# v1.net
KiCad netlist of a schematic drawn in EAGLE
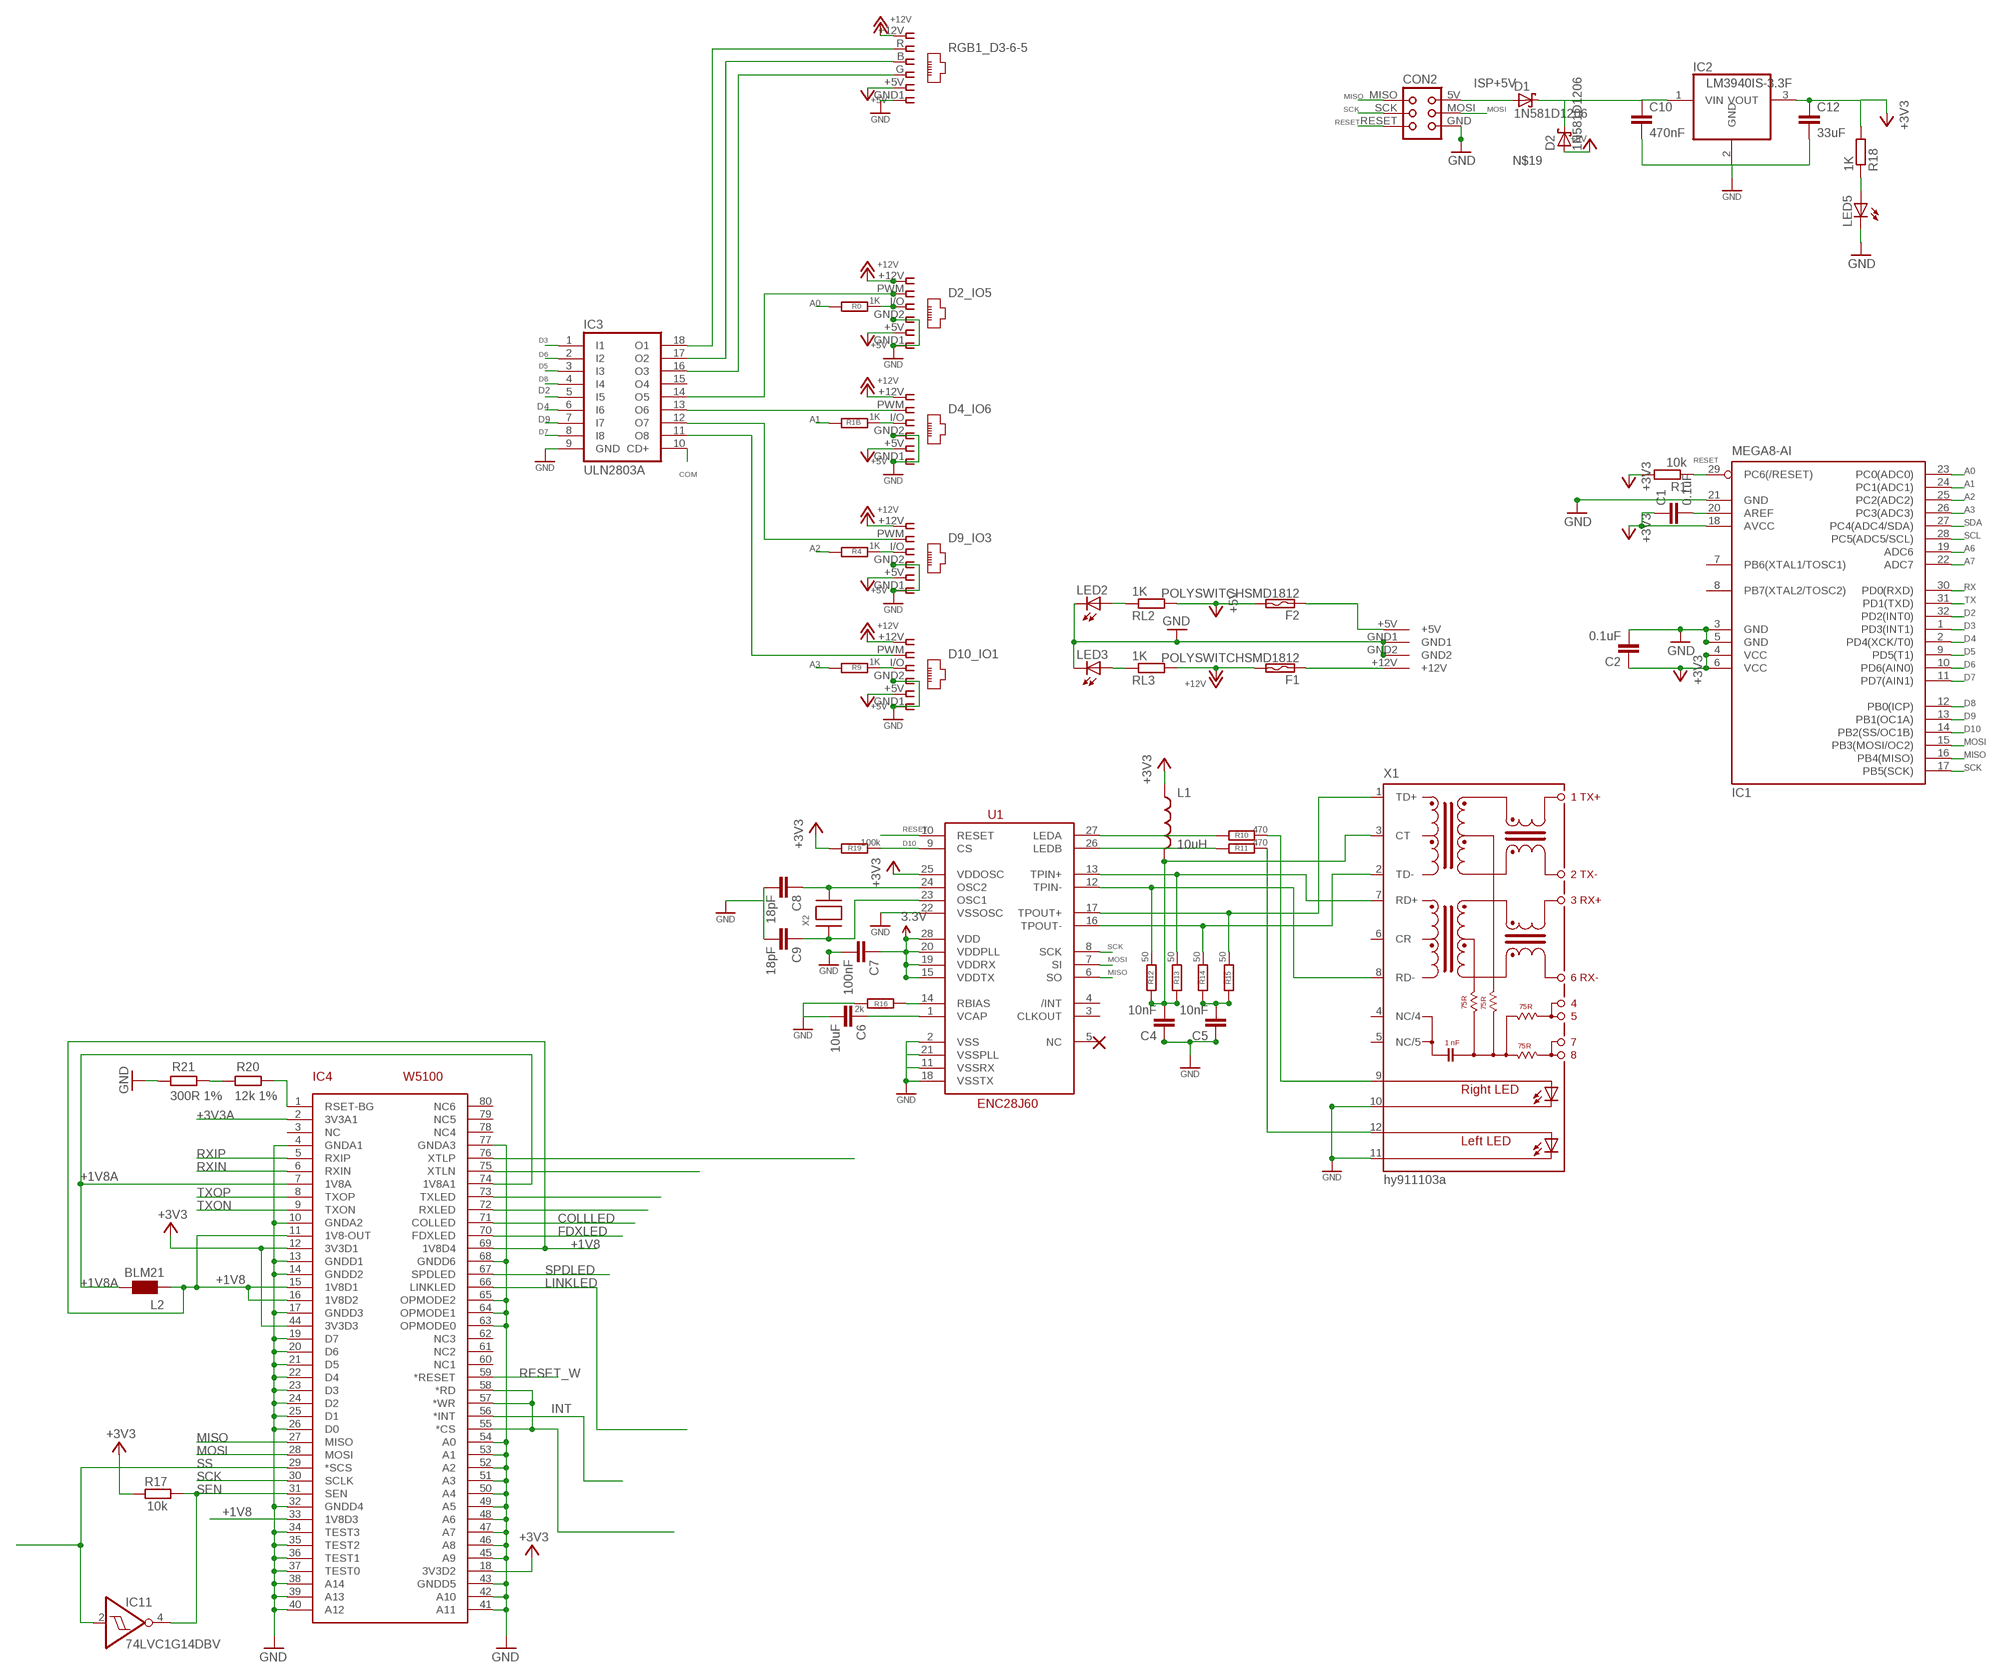
[diagram p0: schematic, sheet 1, part 1 of 2]
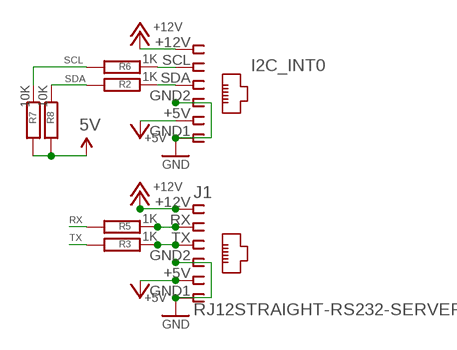
[diagram p1: schematic, sheet 1, part 2 of 2]

(export (version "E")
  (design (tool "Eeschema 10.0.6"))
  (components
    (comp (ref "C1")
      (value "0.1uF")
      (footprint "eagle-import:C1206")
      (libsource (lib "eagle-import") (part "resistor_C-EUC1206"))
    )
    (comp (ref "C2")
      (value "0.1uF")
      (footprint "eagle-import:C1206")
      (libsource (lib "eagle-import") (part "resistor_C-EUC1206"))
    )
    (comp (ref "C4")
      (value "10nF")
      (footprint "eagle-import:C1206")
      (libsource (lib "eagle-import") (part "resistor_C-EUC1206"))
    )
    (comp (ref "C5")
      (value "10nF")
      (footprint "eagle-import:C1206")
      (libsource (lib "eagle-import") (part "resistor_C-EUC1206"))
    )
    (comp (ref "C6")
      (value "10uF")
      (footprint "eagle-import:C1206")
      (libsource (lib "eagle-import") (part "resistor_C-EUC1206"))
    )
    (comp (ref "C7")
      (value "100nF")
      (footprint "eagle-import:C1206")
      (libsource (lib "eagle-import") (part "resistor_C-EUC1206"))
    )
    (comp (ref "C8")
      (value "18pF")
      (footprint "eagle-import:C1206")
      (libsource (lib "eagle-import") (part "resistor_C-EUC1206"))
    )
    (comp (ref "C9")
      (value "18pF")
      (footprint "eagle-import:C1206")
      (libsource (lib "eagle-import") (part "resistor_C-EUC1206"))
    )
    (comp (ref "C10")
      (value "470nF")
      (footprint "eagle-import:C1206")
      (libsource (lib "eagle-import") (part "C-EUC1206"))
    )
    (comp (ref "C12")
      (value "33uF")
      (footprint "eagle-import:1210")
      (libsource (lib "eagle-import") (part "CAP1210"))
    )
    (comp (ref "CON2")
      (value "TINYISPTAG")
      (footprint "eagle-import:TC2030-MCP")
      (libsource (lib "eagle-import") (part "TINYISPTAG"))
    )
    (comp (ref "D1")
      (value "1N581D1206")
      (footprint "eagle-import:LED-1206")
      (libsource (lib "eagle-import") (part "1N581D1206"))
    )
    (comp (ref "D2")
      (value "1N581D1206")
      (footprint "eagle-import:LED-1206")
      (libsource (lib "eagle-import") (part "1N581D1206"))
    )
    (comp (ref "D2_IO5")
      (value "IO5")
      (footprint "eagle-import:RJ12-STRAIGHT")
      (libsource (lib "eagle-import") (part "RJ12STRAIGHT"))
    )
    (comp (ref "D4_IO6")
      (value "IO6")
      (footprint "eagle-import:RJ12-STRAIGHT")
      (libsource (lib "eagle-import") (part "RJ12STRAIGHT"))
    )
    (comp (ref "D9_IO3")
      (value "IO3")
      (footprint "eagle-import:RJ12-STRAIGHT")
      (libsource (lib "eagle-import") (part "RJ12STRAIGHT"))
    )
    (comp (ref "D10_IO1")
      (value "IO1")
      (footprint "eagle-import:RJ12-STRAIGHT")
      (libsource (lib "eagle-import") (part "RJ12STRAIGHT"))
    )
    (comp (ref "F1")
      (value "POLYSWITCHSMD1812")
      (footprint "eagle-import:C1812")
      (libsource (lib "eagle-import") (part "POLYSWITCHSMD1812"))
    )
    (comp (ref "F2")
      (value "POLYSWITCHSMD1812")
      (footprint "eagle-import:C1812")
      (libsource (lib "eagle-import") (part "POLYSWITCHSMD1812"))
    )
    (comp (ref "I2C_INT0")
      (value "I2C")
      (footprint "eagle-import:RJ12-STRAIGHT-I2C")
      (libsource (lib "eagle-import") (part "RJ12STRAIGHT-I2C"))
    )
    (comp (ref "IC1")
      (value "MEGA8-AI")
      (footprint "eagle-import:TQFP32-08")
      (fields (field (name "MPN") "ATMEGA8-16AU"))
      (libsource (lib "eagle-import") (part "MEGA8-AI"))
    )
    (comp (ref "IC2")
      (value "LM3940IS-3.3F")
      (footprint "eagle-import:DD-3")
      (fields (field (name "MF") "TEXAS INSTRUMENTS") (field (name "MPN") "REG1117FAKTTT"))
      (libsource (lib "eagle-import") (part "LM3940IS-3.3F"))
    )
    (comp (ref "IC3")
      (value "ULN2803A")
      (footprint "eagle-import:SO18W")
      (libsource (lib "eagle-import") (part "ULN2803A"))
    )
    (comp (ref "IC4")
      (value "W5100")
      (footprint "eagle-import:SQFP-S-10X10-80")
      (libsource (lib "eagle-import") (part "W5100"))
    )
    (comp (ref "IC11")
      (value "74LVC1G14DBV")
      (footprint "eagle-import:SOT23-5")
      (libsource (lib "eagle-import") (part "741G14DBVLVC"))
    )
    (comp (ref "J1")
      (value "RJ12STRAIGHT-RS232-SERVER")
      (footprint "eagle-import:RJ12-STRAIGHT-RS232")
      (libsource (lib "eagle-import") (part "RJ12STRAIGHT-RS232-SERVER"))
    )
    (comp (ref "L1")
      (value "10uH")
      (footprint "eagle-import:INDUCTOR-1206")
      (libsource (lib "eagle-import") (part "INDUCTORH1206"))
    )
    (comp (ref "L2")
      (value "BLM21")
      (footprint "eagle-import:0805")
      (libsource (lib "eagle-import") (part "WE-CBF_0805"))
    )
    (comp (ref "LED2")
      (value "LED3MM")
      (footprint "eagle-import:LED3MM")
      (libsource (lib "eagle-import") (part "LED3MM"))
    )
    (comp (ref "LED3")
      (value "LED3MM")
      (footprint "eagle-import:LED3MM")
      (libsource (lib "eagle-import") (part "LED3MM"))
    )
    (comp (ref "LED5")
      (value "LED3MM")
      (footprint "eagle-import:LED3MM")
      (libsource (lib "eagle-import") (part "LED3MM"))
    )
    (comp (ref "R0")
      (value "1K")
      (footprint "eagle-import:M1206")
      (libsource (lib "eagle-import") (part "resistor_R-EU_M1206"))
    )
    (comp (ref "R1")
      (value "10k")
      (footprint "eagle-import:M1206")
      (libsource (lib "eagle-import") (part "resistor_R-EU_M1206"))
    )
    (comp (ref "R1B")
      (value "1K")
      (footprint "eagle-import:M1206")
      (libsource (lib "eagle-import") (part "resistor_R-EU_M1206"))
    )
    (comp (ref "R2")
      (value "1K")
      (footprint "eagle-import:M1206")
      (libsource (lib "eagle-import") (part "resistor_R-EU_M1206"))
    )
    (comp (ref "R3")
      (value "1K")
      (footprint "eagle-import:M1206")
      (libsource (lib "eagle-import") (part "resistor_R-EU_M1206"))
    )
    (comp (ref "R4")
      (value "1K")
      (footprint "eagle-import:M1206")
      (libsource (lib "eagle-import") (part "resistor_R-EU_M1206"))
    )
    (comp (ref "R5")
      (value "1K")
      (footprint "eagle-import:M1206")
      (libsource (lib "eagle-import") (part "resistor_R-EU_M1206"))
    )
    (comp (ref "R6")
      (value "1K")
      (footprint "eagle-import:M1206")
      (libsource (lib "eagle-import") (part "resistor_R-EU_M1206"))
    )
    (comp (ref "R7")
      (value "10K")
      (footprint "eagle-import:M1206")
      (libsource (lib "eagle-import") (part "resistor_R-EU_M1206"))
    )
    (comp (ref "R8")
      (value "10K")
      (footprint "eagle-import:M1206")
      (libsource (lib "eagle-import") (part "resistor_R-EU_M1206"))
    )
    (comp (ref "R9")
      (value "1K")
      (footprint "eagle-import:M1206")
      (libsource (lib "eagle-import") (part "resistor_R-EU_M1206"))
    )
    (comp (ref "R10")
      (value "470")
      (footprint "eagle-import:M1206")
      (libsource (lib "eagle-import") (part "resistor_R-EU_M1206"))
    )
    (comp (ref "R11")
      (value "470")
      (footprint "eagle-import:M1206")
      (libsource (lib "eagle-import") (part "resistor_R-EU_M1206"))
    )
    (comp (ref "R12")
      (value "50")
      (footprint "eagle-import:M1206")
      (libsource (lib "eagle-import") (part "resistor_R-EU_M1206"))
    )
    (comp (ref "R13")
      (value "50")
      (footprint "eagle-import:M1206")
      (libsource (lib "eagle-import") (part "resistor_R-EU_M1206"))
    )
    (comp (ref "R14")
      (value "50")
      (footprint "eagle-import:M1206")
      (libsource (lib "eagle-import") (part "resistor_R-EU_M1206"))
    )
    (comp (ref "R15")
      (value "50")
      (footprint "eagle-import:M1206")
      (libsource (lib "eagle-import") (part "resistor_R-EU_M1206"))
    )
    (comp (ref "R16")
      (value "2k")
      (footprint "eagle-import:M1206")
      (libsource (lib "eagle-import") (part "resistor_R-EU_M1206"))
    )
    (comp (ref "R17")
      (value "10k")
      (footprint "eagle-import:R0603-ROUND")
      (libsource (lib "eagle-import") (part "R-EU_0603-RND"))
    )
    (comp (ref "R18")
      (value "1K")
      (footprint "eagle-import:M1206")
      (libsource (lib "eagle-import") (part "resistor_R-EU_M1206"))
    )
    (comp (ref "R19")
      (value "100k")
      (footprint "eagle-import:M1206")
      (libsource (lib "eagle-import") (part "resistor_R-EU_M1206"))
    )
    (comp (ref "R20")
      (value "12k 1%")
      (footprint "eagle-import:R0603-ROUND")
      (libsource (lib "eagle-import") (part "R-EU_0603-RND"))
    )
    (comp (ref "R21")
      (value "300R 1%")
      (footprint "eagle-import:R0603-ROUND")
      (libsource (lib "eagle-import") (part "R-EU_0603-RND"))
    )
    (comp (ref "RGB1_D3-6-5")
      (value "RGB1")
      (footprint "eagle-import:RJ12-STRAIGHT-RGB")
      (libsource (lib "eagle-import") (part "RJ12STRAIGHT-RGB"))
    )
    (comp (ref "RL2")
      (value "1K")
      (footprint "eagle-import:M1206")
      (libsource (lib "eagle-import") (part "resistor_R-EU_M1206"))
    )
    (comp (ref "RL3")
      (value "1K")
      (footprint "eagle-import:M1206")
      (libsource (lib "eagle-import") (part "resistor_R-EU_M1206"))
    )
    (comp (ref "U$2")
      (value "KPJX-4S-S")
      (footprint "eagle-import:KPJX-4S-S")
      (libsource (lib "eagle-import") (part "KPJX-4S-S"))
    )
    (comp (ref "U1")
      (value "ENC28J60SO")
      (footprint "eagle-import:SO28W")
      (libsource (lib "eagle-import") (part "ENC28J60SO"))
    )
    (comp (ref "X1")
      (value "hy911103a")
      (footprint "eagle-import:J1")
      (libsource (lib "eagle-import") (part "J1011F01P"))
    )
    (comp (ref "X2")
      (value "XTALNX5032")
      (footprint "eagle-import:NX5032")
      (libsource (lib "eagle-import") (part "XTALNX5032"))
    )
  )
  (nets
    (net (code "1") (name "+3V3") (class "Default")
      (node (ref "C1") (pin "1") (pinfunction "1_1") (pintype "passive"))
      (node (ref "C12") (pin "1") (pinfunction "1_1") (pintype "passive"))
      (node (ref "C2") (pin "1") (pinfunction "1_1") (pintype "passive"))
      (node (ref "IC1") (pin "18") (pinfunction "AVCC_18") (pintype "power_in"))
      (node (ref "IC1") (pin "4") (pinfunction "VCC_4") (pintype "power_in"))
      (node (ref "IC1") (pin "6") (pinfunction "VCC_6") (pintype "power_in"))
      (node (ref "IC2") (pin "3") (pinfunction "VOUT_3") (pintype "output"))
      (node (ref "IC4") (pin "12") (pinfunction "3V3D1_12") (pintype "power_in"))
      (node (ref "IC4") (pin "18") (pinfunction "3V3D2_18") (pintype "power_in"))
      (node (ref "IC4") (pin "44") (pinfunction "3V3D3_44") (pintype "power_in"))
      (node (ref "L1") (pin "P$1") (pinfunction "1_P$1") (pintype "passive"))
      (node (ref "R1") (pin "2") (pinfunction "2_2") (pintype "passive"))
      (node (ref "R17") (pin "1") (pinfunction "1_1") (pintype "passive"))
      (node (ref "R18") (pin "2") (pinfunction "2_2") (pintype "passive"))
      (node (ref "R19") (pin "2") (pinfunction "2_2") (pintype "passive"))
      (node (ref "U1") (pin "25") (pinfunction "VDDOSC_25") (pintype "bidirectional"))
    )
    (net (code "2") (name "+5V") (class "Default")
      (node (ref "D10_IO1") (pin "+5V") (pinfunction "5_+5V") (pintype "power_in"))
      (node (ref "D2") (pin "A") (pinfunction "A_A") (pintype "passive"))
      (node (ref "D2_IO5") (pin "+5V") (pinfunction "5_+5V") (pintype "power_in"))
      (node (ref "D4_IO6") (pin "+5V") (pinfunction "5_+5V") (pintype "power_in"))
      (node (ref "D9_IO3") (pin "+5V") (pinfunction "5_+5V") (pintype "power_in"))
      (node (ref "F2") (pin "2") (pinfunction "2_2") (pintype "passive"))
      (node (ref "I2C_INT0") (pin "+5V") (pinfunction "5_+5V") (pintype "power_in"))
      (node (ref "J1") (pin "+5V") (pinfunction "5_+5V") (pintype "power_in"))
      (node (ref "RGB1_D3-6-5") (pin "+5V") (pinfunction "5_+5V") (pintype "power_in"))
      (node (ref "RL2") (pin "2") (pinfunction "2_2") (pintype "passive"))
    )
    (net (code "3") (name "+12V") (class "Default")
      (node (ref "D10_IO1") (pin "+12V") (pinfunction "1_+12V") (pintype "power_in"))
      (node (ref "D2_IO5") (pin "+12V") (pinfunction "1_+12V") (pintype "power_in"))
      (node (ref "D4_IO6") (pin "+12V") (pinfunction "1_+12V") (pintype "power_in"))
      (node (ref "D9_IO3") (pin "+12V") (pinfunction "1_+12V") (pintype "power_in"))
      (node (ref "F1") (pin "2") (pinfunction "2_2") (pintype "passive"))
      (node (ref "I2C_INT0") (pin "+12V") (pinfunction "1_+12V") (pintype "power_in"))
      (node (ref "J1") (pin "+12V") (pinfunction "1_+12V") (pintype "power_in"))
      (node (ref "RGB1_D3-6-5") (pin "+12V") (pinfunction "1_+12V") (pintype "power_in"))
      (node (ref "RL3") (pin "2") (pinfunction "2_2") (pintype "passive"))
    )
    (net (code "4") (name "/+1V8") (class "Default")
      (node (ref "IC4") (pin "11") (pinfunction "1V8-OUT_11") (pintype "power_in"))
      (node (ref "IC4") (pin "15") (pinfunction "1V8D1_15") (pintype "power_in"))
      (node (ref "IC4") (pin "16") (pinfunction "1V8D2_16") (pintype "power_in"))
      (node (ref "IC4") (pin "33") (pinfunction "1V8D3_33") (pintype "power_in"))
      (node (ref "IC4") (pin "69") (pinfunction "1V8D4_69") (pintype "power_in"))
      (node (ref "L2") (pin "1") (pinfunction "1_1") (pintype "passive"))
    )
    (net (code "5") (name "/+1V8A") (class "Default")
      (node (ref "IC4") (pin "7") (pinfunction "1V8A_7") (pintype "power_in"))
      (node (ref "IC4") (pin "74") (pinfunction "1V8A1_74") (pintype "power_in"))
      (node (ref "L2") (pin "2") (pinfunction "2_2") (pintype "passive"))
    )
    (net (code "6") (name "/+3V3A") (class "Default")
      (node (ref "IC4") (pin "2") (pinfunction "3V3A1_2") (pintype "power_in"))
    )
    (net (code "7") (name "/A0") (class "Default")
      (node (ref "IC1") (pin "23") (pinfunction "PC0(ADC0)_23") (pintype "bidirectional"))
      (node (ref "R0") (pin "2") (pinfunction "2_2") (pintype "passive"))
    )
    (net (code "8") (name "/A1") (class "Default")
      (node (ref "IC1") (pin "24") (pinfunction "PC1(ADC1)_24") (pintype "bidirectional"))
      (node (ref "R1B") (pin "2") (pinfunction "2_2") (pintype "passive"))
    )
    (net (code "9") (name "/A2") (class "Default")
      (node (ref "IC1") (pin "25") (pinfunction "PC2(ADC2)_25") (pintype "bidirectional"))
      (node (ref "R4") (pin "2") (pinfunction "2_2") (pintype "passive"))
    )
    (net (code "10") (name "/A3") (class "Default")
      (node (ref "IC1") (pin "26") (pinfunction "PC3(ADC3)_26") (pintype "bidirectional"))
      (node (ref "R9") (pin "2") (pinfunction "2_2") (pintype "passive"))
    )
    (net (code "11") (name "/A6") (class "Default")
      (node (ref "IC1") (pin "19") (pinfunction "ADC6_19") (pintype "bidirectional"))
    )
    (net (code "12") (name "/A7") (class "Default")
      (node (ref "IC1") (pin "22") (pinfunction "ADC7_22") (pintype "bidirectional"))
    )
    (net (code "13") (name "/COLLLED") (class "Default")
      (node (ref "IC4") (pin "71") (pinfunction "COLLED_71") (pintype "output"))
    )
    (net (code "14") (name "/COM") (class "Default")
      (node (ref "IC3") (pin "10") (pinfunction "CD+_10") (pintype "passive"))
    )
    (net (code "15") (name "/D2") (class "Default")
      (node (ref "IC1") (pin "32") (pinfunction "PD2(INT0)_32") (pintype "bidirectional"))
      (node (ref "IC3") (pin "5") (pinfunction "I5_5") (pintype "input"))
    )
    (net (code "16") (name "/D3") (class "Default")
      (node (ref "IC1") (pin "1") (pinfunction "PD3(INT1)_1") (pintype "bidirectional"))
      (node (ref "IC3") (pin "1") (pinfunction "I1_1") (pintype "input"))
    )
    (net (code "17") (name "/D4") (class "Default")
      (node (ref "IC1") (pin "2") (pinfunction "PD4(XCK/T0)_2") (pintype "bidirectional"))
      (node (ref "IC3") (pin "6") (pinfunction "I6_6") (pintype "input"))
    )
    (net (code "18") (name "/D5") (class "Default")
      (node (ref "IC1") (pin "9") (pinfunction "PD5(T1)_9") (pintype "bidirectional"))
      (node (ref "IC3") (pin "3") (pinfunction "I3_3") (pintype "input"))
    )
    (net (code "19") (name "/D6") (class "Default")
      (node (ref "IC1") (pin "10") (pinfunction "PD6(AIN0)_10") (pintype "bidirectional"))
      (node (ref "IC3") (pin "2") (pinfunction "I2_2") (pintype "input"))
    )
    (net (code "20") (name "/D7") (class "Default")
      (node (ref "IC1") (pin "11") (pinfunction "PD7(AIN1)_11") (pintype "bidirectional"))
      (node (ref "IC3") (pin "8") (pinfunction "I8_8") (pintype "input"))
    )
    (net (code "21") (name "/D8") (class "Default")
      (node (ref "IC1") (pin "12") (pinfunction "PB0(ICP)_12") (pintype "bidirectional"))
      (node (ref "IC3") (pin "4") (pinfunction "I4_4") (pintype "input"))
    )
    (net (code "22") (name "/D9") (class "Default")
      (node (ref "IC1") (pin "13") (pinfunction "PB1(OC1A)_13") (pintype "bidirectional"))
      (node (ref "IC3") (pin "7") (pinfunction "I7_7") (pintype "input"))
    )
    (net (code "23") (name "/D10") (class "Default")
      (node (ref "IC1") (pin "14") (pinfunction "PB2(SS/OC1B)_14") (pintype "bidirectional"))
      (node (ref "R19") (pin "1") (pinfunction "1_1") (pintype "passive"))
      (node (ref "U1") (pin "9") (pinfunction "CS_9") (pintype "bidirectional"))
    )
    (net (code "24") (name "/FDXLED") (class "Default")
      (node (ref "IC4") (pin "70") (pinfunction "FDXLED_70") (pintype "output"))
    )
    (net (code "25") (name "/INT") (class "Default")
      (node (ref "IC4") (pin "56") (pinfunction "*INT_56") (pintype "input"))
    )
    (net (code "26") (name "/ISP+5V") (class "Default")
      (node (ref "CON2") (pin "5V") (pinfunction "VCC_5V") (pintype "passive"))
      (node (ref "D1") (pin "A") (pinfunction "A_A") (pintype "passive"))
    )
    (net (code "27") (name "/LINKLED") (class "Default")
      (node (ref "IC4") (pin "66") (pinfunction "LINKLED_66") (pintype "output"))
    )
    (net (code "28") (name "/MISO") (class "Default")
      (node (ref "CON2") (pin "MISO") (pinfunction "MISO_MISO") (pintype "passive"))
      (node (ref "IC1") (pin "16") (pinfunction "PB4(MISO)_16") (pintype "bidirectional"))
      (node (ref "IC4") (pin "27") (pinfunction "MISO_27") (pintype "input"))
      (node (ref "U1") (pin "6") (pinfunction "SO_6") (pintype "bidirectional"))
    )
    (net (code "29") (name "/MOSI") (class "Default")
      (node (ref "CON2") (pin "MOSI") (pinfunction "MOSI_MOSI") (pintype "passive"))
      (node (ref "IC1") (pin "15") (pinfunction "PB3(MOSI/OC2)_15") (pintype "bidirectional"))
      (node (ref "IC4") (pin "28") (pinfunction "MOSI_28") (pintype "output"))
      (node (ref "U1") (pin "7") (pinfunction "SI_7") (pintype "bidirectional"))
    )
    (net (code "30") (name "/N$19") (class "Default")
      (node (ref "C10") (pin "1") (pinfunction "1_1") (pintype "passive"))
      (node (ref "D1") (pin "C") (pinfunction "C_C") (pintype "passive"))
      (node (ref "D2") (pin "C") (pinfunction "C_C") (pintype "passive"))
      (node (ref "IC2") (pin "1") (pinfunction "VIN_1") (pintype "input"))
    )
    (net (code "31") (name "/RESET") (class "Default")
      (node (ref "CON2") (pin "RESET") (pinfunction "RESET_RESET") (pintype "passive"))
      (node (ref "IC1") (pin "29") (pinfunction "PC6(/RESET)_29") (pintype "bidirectional"))
      (node (ref "R1") (pin "1") (pinfunction "1_1") (pintype "passive"))
      (node (ref "U1") (pin "10") (pinfunction "RESET_10") (pintype "bidirectional"))
    )
    (net (code "32") (name "/RESET_W") (class "Default")
      (node (ref "IC4") (pin "59") (pinfunction "*RESET_59") (pintype "input"))
    )
    (net (code "33") (name "/RX") (class "Default")
      (node (ref "IC1") (pin "30") (pinfunction "PD0(RXD)_30") (pintype "bidirectional"))
      (node (ref "R5") (pin "2") (pinfunction "2_2") (pintype "passive"))
    )
    (net (code "34") (name "/RXIN") (class "Default")
      (node (ref "IC4") (pin "6") (pinfunction "RXIN_6") (pintype "input"))
    )
    (net (code "35") (name "/RXIP") (class "Default")
      (node (ref "IC4") (pin "5") (pinfunction "RXIP_5") (pintype "input"))
    )
    (net (code "36") (name "/SCK") (class "Default")
      (node (ref "CON2") (pin "SCK") (pinfunction "SCK_SCK") (pintype "passive"))
      (node (ref "IC1") (pin "17") (pinfunction "PB5(SCK)_17") (pintype "bidirectional"))
      (node (ref "IC4") (pin "30") (pinfunction "SCLK_30") (pintype "input"))
      (node (ref "U1") (pin "8") (pinfunction "SCK_8") (pintype "bidirectional"))
    )
    (net (code "37") (name "/SCL") (class "Default")
      (node (ref "IC1") (pin "28") (pinfunction "PC5(ADC5/SCL)_28") (pintype "bidirectional"))
      (node (ref "R6") (pin "2") (pinfunction "2_2") (pintype "passive"))
      (node (ref "R7") (pin "1") (pinfunction "1_1") (pintype "passive"))
    )
    (net (code "38") (name "/SDA") (class "Default")
      (node (ref "IC1") (pin "27") (pinfunction "PC4(ADC4/SDA)_27") (pintype "bidirectional"))
      (node (ref "R2") (pin "2") (pinfunction "2_2") (pintype "passive"))
      (node (ref "R8") (pin "1") (pinfunction "1_1") (pintype "passive"))
    )
    (net (code "39") (name "/SEN") (class "Default")
      (node (ref "IC11") (pin "4") (pinfunction "O_4") (pintype "output"))
      (node (ref "IC4") (pin "31") (pinfunction "SEN_31") (pintype "input"))
      (node (ref "R17") (pin "2") (pinfunction "2_2") (pintype "passive"))
    )
    (net (code "40") (name "/SPDLED") (class "Default")
      (node (ref "IC4") (pin "67") (pinfunction "SPDLED_67") (pintype "output"))
    )
    (net (code "41") (name "/SS") (class "Default")
      (node (ref "IC11") (pin "2") (pinfunction "I_2") (pintype "input"))
      (node (ref "IC4") (pin "29") (pinfunction "*SCS_29") (pintype "input"))
    )
    (net (code "42") (name "/TX") (class "Default")
      (node (ref "IC1") (pin "31") (pinfunction "PD1(TXD)_31") (pintype "bidirectional"))
      (node (ref "R3") (pin "2") (pinfunction "2_2") (pintype "passive"))
    )
    (net (code "43") (name "/TXON") (class "Default")
      (node (ref "IC4") (pin "9") (pinfunction "TXON_9") (pintype "output"))
    )
    (net (code "44") (name "/TXOP") (class "Default")
      (node (ref "IC4") (pin "8") (pinfunction "TXOP_8") (pintype "output"))
    )
    (net (code "45") (name "3.3V") (class "Default")
      (node (ref "C7") (pin "1") (pinfunction "1_1") (pintype "passive"))
      (node (ref "U1") (pin "15") (pinfunction "VDDTX_15") (pintype "bidirectional"))
      (node (ref "U1") (pin "19") (pinfunction "VDDRX_19") (pintype "bidirectional"))
      (node (ref "U1") (pin "20") (pinfunction "VDDPLL_20") (pintype "bidirectional"))
      (node (ref "U1") (pin "28") (pinfunction "VDD_28") (pintype "bidirectional"))
    )
    (net (code "46") (name "5V") (class "Default")
      (node (ref "R7") (pin "2") (pinfunction "2_2") (pintype "passive"))
      (node (ref "R8") (pin "2") (pinfunction "2_2") (pintype "passive"))
    )
    (net (code "47") (name "GND") (class "Default")
      (node (ref "C10") (pin "2") (pinfunction "2_2") (pintype "passive"))
      (node (ref "C12") (pin "2") (pinfunction "2_2") (pintype "passive"))
      (node (ref "C2") (pin "2") (pinfunction "2_2") (pintype "passive"))
      (node (ref "C4") (pin "1") (pinfunction "1_1") (pintype "passive"))
      (node (ref "C5") (pin "1") (pinfunction "1_1") (pintype "passive"))
      (node (ref "C6") (pin "2") (pinfunction "2_2") (pintype "passive"))
      (node (ref "C7") (pin "2") (pinfunction "2_2") (pintype "passive"))
      (node (ref "C8") (pin "2") (pinfunction "2_2") (pintype "passive"))
      (node (ref "C9") (pin "2") (pinfunction "2_2") (pintype "passive"))
      (node (ref "CON2") (pin "GND") (pinfunction "GND_GND") (pintype "passive"))
      (node (ref "D10_IO1") (pin "GND1") (pinfunction "6_GND1") (pintype "power_in"))
      (node (ref "D10_IO1") (pin "GND2") (pinfunction "4_GND2") (pintype "power_in"))
      (node (ref "D2_IO5") (pin "GND1") (pinfunction "6_GND1") (pintype "power_in"))
      (node (ref "D2_IO5") (pin "GND2") (pinfunction "4_GND2") (pintype "power_in"))
      (node (ref "D4_IO6") (pin "GND1") (pinfunction "6_GND1") (pintype "power_in"))
      (node (ref "D4_IO6") (pin "GND2") (pinfunction "4_GND2") (pintype "power_in"))
      (node (ref "D9_IO3") (pin "GND1") (pinfunction "6_GND1") (pintype "power_in"))
      (node (ref "D9_IO3") (pin "GND2") (pinfunction "4_GND2") (pintype "power_in"))
      (node (ref "I2C_INT0") (pin "GND1") (pinfunction "6_GND1") (pintype "power_in"))
      (node (ref "I2C_INT0") (pin "GND2") (pinfunction "4_GND2") (pintype "power_in"))
      (node (ref "IC1") (pin "21") (pinfunction "GND_21") (pintype "power_in"))
      (node (ref "IC1") (pin "3") (pinfunction "GND_3") (pintype "power_in"))
      (node (ref "IC1") (pin "5") (pinfunction "GND_5") (pintype "power_in"))
      (node (ref "IC2") (pin "2") (pinfunction "GND_2") (pintype "power_in"))
      (node (ref "IC3") (pin "9") (pinfunction "GND_9") (pintype "power_in"))
      (node (ref "IC4") (pin "10") (pinfunction "GNDA2_10") (pintype "power_in"))
      (node (ref "IC4") (pin "13") (pinfunction "GNDD1_13") (pintype "power_in"))
      (node (ref "IC4") (pin "14") (pinfunction "GNDD2_14") (pintype "power_in"))
      (node (ref "IC4") (pin "17") (pinfunction "GNDD3_17") (pintype "power_in"))
      (node (ref "IC4") (pin "19") (pinfunction "D7_19") (pintype "input"))
      (node (ref "IC4") (pin "20") (pinfunction "D6_20") (pintype "input"))
      (node (ref "IC4") (pin "21") (pinfunction "D5_21") (pintype "input"))
      (node (ref "IC4") (pin "22") (pinfunction "D4_22") (pintype "input"))
      (node (ref "IC4") (pin "23") (pinfunction "D3_23") (pintype "input"))
      (node (ref "IC4") (pin "24") (pinfunction "D2_24") (pintype "input"))
      (node (ref "IC4") (pin "25") (pinfunction "D1_25") (pintype "input"))
      (node (ref "IC4") (pin "26") (pinfunction "D0_26") (pintype "input"))
      (node (ref "IC4") (pin "32") (pinfunction "GNDD4_32") (pintype "power_in"))
      (node (ref "IC4") (pin "34") (pinfunction "TEST3_34") (pintype "input"))
      (node (ref "IC4") (pin "35") (pinfunction "TEST2_35") (pintype "input"))
      (node (ref "IC4") (pin "36") (pinfunction "TEST1_36") (pintype "input"))
      (node (ref "IC4") (pin "37") (pinfunction "TEST0_37") (pintype "input"))
      (node (ref "IC4") (pin "38") (pinfunction "A14_38") (pintype "input"))
      (node (ref "IC4") (pin "39") (pinfunction "A13_39") (pintype "input"))
      (node (ref "IC4") (pin "4") (pinfunction "GNDA1_4") (pintype "power_in"))
      (node (ref "IC4") (pin "40") (pinfunction "A12_40") (pintype "input"))
      (node (ref "IC4") (pin "41") (pinfunction "A11_41") (pintype "input"))
      (node (ref "IC4") (pin "42") (pinfunction "A10_42") (pintype "input"))
      (node (ref "IC4") (pin "43") (pinfunction "GNDD5_43") (pintype "power_in"))
      (node (ref "IC4") (pin "45") (pinfunction "A9_45") (pintype "input"))
      (node (ref "IC4") (pin "46") (pinfunction "A8_46") (pintype "input"))
      (node (ref "IC4") (pin "47") (pinfunction "A7_47") (pintype "input"))
      (node (ref "IC4") (pin "48") (pinfunction "A6_48") (pintype "input"))
      (node (ref "IC4") (pin "49") (pinfunction "A5_49") (pintype "input"))
      (node (ref "IC4") (pin "50") (pinfunction "A4_50") (pintype "input"))
      (node (ref "IC4") (pin "51") (pinfunction "A3_51") (pintype "input"))
      (node (ref "IC4") (pin "52") (pinfunction "A2_52") (pintype "input"))
      (node (ref "IC4") (pin "53") (pinfunction "A1_53") (pintype "input"))
      (node (ref "IC4") (pin "54") (pinfunction "A0_54") (pintype "input"))
      (node (ref "IC4") (pin "63") (pinfunction "OPMODE0_63") (pintype "input"))
      (node (ref "IC4") (pin "64") (pinfunction "OPMODE1_64") (pintype "input"))
      (node (ref "IC4") (pin "65") (pinfunction "OPMODE2_65") (pintype "input"))
      (node (ref "IC4") (pin "68") (pinfunction "GNDD6_68") (pintype "power_in"))
      (node (ref "IC4") (pin "77") (pinfunction "GNDA3_77") (pintype "power_in"))
      (node (ref "J1") (pin "GND1") (pinfunction "6_GND1") (pintype "power_in"))
      (node (ref "J1") (pin "GND2") (pinfunction "4_GND2") (pintype "power_in"))
      (node (ref "LED2") (pin "K") (pinfunction "C_K") (pintype "passive"))
      (node (ref "LED3") (pin "K") (pinfunction "C_K") (pintype "passive"))
      (node (ref "LED5") (pin "K") (pinfunction "C_K") (pintype "passive"))
      (node (ref "R16") (pin "1") (pinfunction "1_1") (pintype "passive"))
      (node (ref "R21") (pin "2") (pinfunction "2_2") (pintype "passive"))
      (node (ref "RGB1_D3-6-5") (pin "GND1") (pinfunction "6_GND1") (pintype "power_in"))
      (node (ref "U$2") (pin "GND1") (pinfunction "GND1_GND1") (pintype "input"))
      (node (ref "U$2") (pin "GND2") (pinfunction "GND2_GND2") (pintype "input"))
      (node (ref "U1") (pin "11") (pinfunction "VSSRX_11") (pintype "bidirectional"))
      (node (ref "U1") (pin "18") (pinfunction "VSSTX_18") (pintype "bidirectional"))
      (node (ref "U1") (pin "2") (pinfunction "VSS_2") (pintype "bidirectional"))
      (node (ref "U1") (pin "21") (pinfunction "VSSPLL_21") (pintype "bidirectional"))
      (node (ref "U1") (pin "22") (pinfunction "VSSOSC_22") (pintype "bidirectional"))
      (node (ref "X1") (pin "10") (pinfunction "C-R_10") (pintype "passive"))
      (node (ref "X1") (pin "11") (pinfunction "C-L_11") (pintype "passive"))
    )
    (net (code "48") (name "Net-(C5-Pad2)") (class "Default")
      (node (ref "C5") (pin "2") (pinfunction "2_2") (pintype "passive"))
      (node (ref "R14") (pin "2") (pinfunction "2_2") (pintype "passive"))
      (node (ref "R15") (pin "2") (pinfunction "2_2") (pintype "passive"))
    )
    (net (code "49") (name "Net-(D2_IO5-2)") (class "Default")
      (node (ref "D2_IO5") (pin "PWM") (pinfunction "2_PWM") (pintype "bidirectional"))
      (node (ref "IC3") (pin "14") (pinfunction "O5_14") (pintype "open_collector"))
    )
    (net (code "50") (name "Net-(D2_IO5-3)") (class "Default")
      (node (ref "D2_IO5") (pin "I/O") (pinfunction "3_I/O") (pintype "bidirectional"))
      (node (ref "R0") (pin "1") (pinfunction "1_1") (pintype "passive"))
    )
    (net (code "51") (name "Net-(D4_IO6-2)") (class "Default")
      (node (ref "D4_IO6") (pin "PWM") (pinfunction "2_PWM") (pintype "bidirectional"))
      (node (ref "IC3") (pin "13") (pinfunction "O6_13") (pintype "open_collector"))
    )
    (net (code "52") (name "Net-(D4_IO6-3)") (class "Default")
      (node (ref "D4_IO6") (pin "I/O") (pinfunction "3_I/O") (pintype "bidirectional"))
      (node (ref "R1B") (pin "1") (pinfunction "1_1") (pintype "passive"))
    )
    (net (code "53") (name "Net-(D9_IO3-2)") (class "Default")
      (node (ref "D9_IO3") (pin "PWM") (pinfunction "2_PWM") (pintype "bidirectional"))
      (node (ref "IC3") (pin "12") (pinfunction "O7_12") (pintype "open_collector"))
    )
    (net (code "54") (name "Net-(D9_IO3-3)") (class "Default")
      (node (ref "D9_IO3") (pin "I/O") (pinfunction "3_I/O") (pintype "bidirectional"))
      (node (ref "R4") (pin "1") (pinfunction "1_1") (pintype "passive"))
    )
    (net (code "55") (name "Net-(D10_IO1-2)") (class "Default")
      (node (ref "D10_IO1") (pin "PWM") (pinfunction "2_PWM") (pintype "bidirectional"))
      (node (ref "IC3") (pin "11") (pinfunction "O8_11") (pintype "open_collector"))
    )
    (net (code "56") (name "Net-(D10_IO1-3)") (class "Default")
      (node (ref "D10_IO1") (pin "I/O") (pinfunction "3_I/O") (pintype "bidirectional"))
      (node (ref "R9") (pin "1") (pinfunction "1_1") (pintype "passive"))
    )
    (net (code "57") (name "Net-(F1-Pad1)") (class "Default")
      (node (ref "F1") (pin "1") (pinfunction "1_1") (pintype "passive"))
      (node (ref "U$2") (pin "+12V") (pinfunction "+12V_+12V") (pintype "power_in"))
    )
    (net (code "58") (name "Net-(F2-Pad1)") (class "Default")
      (node (ref "F2") (pin "1") (pinfunction "1_1") (pintype "passive"))
      (node (ref "U$2") (pin "+5V") (pinfunction "+5V_+5V") (pintype "power_in"))
    )
    (net (code "59") (name "Net-(I2C_INT0-2)") (class "Default")
      (node (ref "I2C_INT0") (pin "SCL") (pinfunction "2_SCL") (pintype "bidirectional"))
      (node (ref "R6") (pin "1") (pinfunction "1_1") (pintype "passive"))
    )
    (net (code "60") (name "Net-(I2C_INT0-3)") (class "Default")
      (node (ref "I2C_INT0") (pin "SDA") (pinfunction "3_SDA") (pintype "bidirectional"))
      (node (ref "R2") (pin "1") (pinfunction "1_1") (pintype "passive"))
    )
    (net (code "61") (name "Net-(IC1-AREF)") (class "Default")
      (node (ref "C1") (pin "2") (pinfunction "2_2") (pintype "passive"))
      (node (ref "IC1") (pin "20") (pinfunction "AREF_20") (pintype "passive"))
    )
    (net (code "62") (name "Net-(IC3-O1)") (class "Default")
      (node (ref "IC3") (pin "18") (pinfunction "O1_18") (pintype "open_collector"))
      (node (ref "RGB1_D3-6-5") (pin "R") (pinfunction "2_R") (pintype "bidirectional"))
    )
    (net (code "63") (name "Net-(IC3-O2)") (class "Default")
      (node (ref "IC3") (pin "17") (pinfunction "O2_17") (pintype "open_collector"))
      (node (ref "RGB1_D3-6-5") (pin "B") (pinfunction "3_B") (pintype "bidirectional"))
    )
    (net (code "64") (name "Net-(IC3-O3)") (class "Default")
      (node (ref "IC3") (pin "16") (pinfunction "O3_16") (pintype "open_collector"))
      (node (ref "RGB1_D3-6-5") (pin "G") (pinfunction "4_G") (pintype "power_in"))
    )
    (net (code "65") (name "Net-(IC4-*CS)") (class "Default")
      (node (ref "IC4") (pin "55") (pinfunction "*CS_55") (pintype "input"))
      (node (ref "IC4") (pin "57") (pinfunction "*WR_57") (pintype "input"))
      (node (ref "IC4") (pin "58") (pinfunction "*RD_58") (pintype "input"))
    )
    (net (code "66") (name "Net-(IC4-RSET-BG)") (class "Default")
      (node (ref "IC4") (pin "1") (pinfunction "RSET-BG_1") (pintype "input"))
      (node (ref "R20") (pin "1") (pinfunction "1_1") (pintype "passive"))
    )
    (net (code "67") (name "Net-(J1-2)") (class "Default")
      (node (ref "J1") (pin "RX") (pinfunction "2_RX") (pintype "bidirectional"))
      (node (ref "R5") (pin "1") (pinfunction "1_1") (pintype "passive"))
    )
    (net (code "68") (name "Net-(J1-3)") (class "Default")
      (node (ref "J1") (pin "TX") (pinfunction "3_TX") (pintype "bidirectional"))
      (node (ref "R3") (pin "1") (pinfunction "1_1") (pintype "passive"))
    )
    (net (code "69") (name "Net-(L1-2)") (class "Default")
      (node (ref "C4") (pin "2") (pinfunction "2_2") (pintype "passive"))
      (node (ref "L1") (pin "P$2") (pinfunction "2_P$2") (pintype "passive"))
      (node (ref "R12") (pin "2") (pinfunction "2_2") (pintype "passive"))
      (node (ref "R13") (pin "2") (pinfunction "2_2") (pintype "passive"))
      (node (ref "X1") (pin "3") (pinfunction "CT_3") (pintype "input"))
    )
    (net (code "70") (name "Net-(LED2-PadA)") (class "Default")
      (node (ref "LED2") (pin "A") (pinfunction "A_A") (pintype "passive"))
      (node (ref "RL2") (pin "1") (pinfunction "1_1") (pintype "passive"))
    )
    (net (code "71") (name "Net-(LED3-PadA)") (class "Default")
      (node (ref "LED3") (pin "A") (pinfunction "A_A") (pintype "passive"))
      (node (ref "RL3") (pin "1") (pinfunction "1_1") (pintype "passive"))
    )
    (net (code "72") (name "Net-(LED5-PadA)") (class "Default")
      (node (ref "LED5") (pin "A") (pinfunction "A_A") (pintype "passive"))
      (node (ref "R18") (pin "1") (pinfunction "1_1") (pintype "passive"))
    )
    (net (code "73") (name "Net-(R20-Pad2)") (class "Default")
      (node (ref "R20") (pin "2") (pinfunction "2_2") (pintype "passive"))
      (node (ref "R21") (pin "1") (pinfunction "1_1") (pintype "passive"))
    )
    (net (code "74") (name "Net-(U1-LEDA)") (class "Default")
      (node (ref "R10") (pin "2") (pinfunction "2_2") (pintype "passive"))
      (node (ref "U1") (pin "27") (pinfunction "LEDA_27") (pintype "bidirectional"))
    )
    (net (code "75") (name "Net-(U1-LEDB)") (class "Default")
      (node (ref "R11") (pin "2") (pinfunction "2_2") (pintype "passive"))
      (node (ref "U1") (pin "26") (pinfunction "LEDB_26") (pintype "bidirectional"))
    )
    (net (code "76") (name "Net-(U1-OSC1)") (class "Default")
      (node (ref "C9") (pin "1") (pinfunction "1_1") (pintype "passive"))
      (node (ref "U1") (pin "23") (pinfunction "OSC1_23") (pintype "bidirectional"))
      (node (ref "X2") (pin "P$1") (pinfunction "P$1_P$1") (pintype "bidirectional"))
    )
    (net (code "77") (name "Net-(U1-OSC2)") (class "Default")
      (node (ref "C8") (pin "1") (pinfunction "1_1") (pintype "passive"))
      (node (ref "U1") (pin "24") (pinfunction "OSC2_24") (pintype "bidirectional"))
      (node (ref "X2") (pin "P$2") (pinfunction "P$2_P$2") (pintype "bidirectional"))
    )
    (net (code "78") (name "Net-(U1-RBIAS)") (class "Default")
      (node (ref "R16") (pin "2") (pinfunction "2_2") (pintype "passive"))
      (node (ref "U1") (pin "14") (pinfunction "RBIAS_14") (pintype "bidirectional"))
    )
    (net (code "79") (name "Net-(U1-TPIN+)") (class "Default")
      (node (ref "R13") (pin "1") (pinfunction "1_1") (pintype "passive"))
      (node (ref "U1") (pin "13") (pinfunction "TPIN+_13") (pintype "bidirectional"))
      (node (ref "X1") (pin "7") (pinfunction "RD+_7") (pintype "input"))
    )
    (net (code "80") (name "Net-(U1-TPIN-)") (class "Default")
      (node (ref "R12") (pin "1") (pinfunction "1_1") (pintype "passive"))
      (node (ref "U1") (pin "12") (pinfunction "TPIN-_12") (pintype "bidirectional"))
      (node (ref "X1") (pin "8") (pinfunction "RD-_8") (pintype "input"))
    )
    (net (code "81") (name "Net-(U1-TPOUT+)") (class "Default")
      (node (ref "R15") (pin "1") (pinfunction "1_1") (pintype "passive"))
      (node (ref "U1") (pin "17") (pinfunction "TPOUT+_17") (pintype "bidirectional"))
      (node (ref "X1") (pin "1") (pinfunction "TD+_1") (pintype "input"))
    )
    (net (code "82") (name "Net-(U1-TPOUT-)") (class "Default")
      (node (ref "R14") (pin "1") (pinfunction "1_1") (pintype "passive"))
      (node (ref "U1") (pin "16") (pinfunction "TPOUT-_16") (pintype "bidirectional"))
      (node (ref "X1") (pin "2") (pinfunction "TD-_2") (pintype "input"))
    )
    (net (code "83") (name "Net-(U1-VCAP)") (class "Default")
      (node (ref "C6") (pin "1") (pinfunction "1_1") (pintype "passive"))
      (node (ref "U1") (pin "1") (pinfunction "VCAP_1") (pintype "bidirectional"))
    )
    (net (code "84") (name "Net-(X1-A-R)") (class "Default")
      (node (ref "R10") (pin "1") (pinfunction "1_1") (pintype "passive"))
      (node (ref "X1") (pin "9") (pinfunction "A-R_9") (pintype "passive"))
    )
    (net (code "85") (name "Net-(X1-AL)") (class "Default")
      (node (ref "R11") (pin "1") (pinfunction "1_1") (pintype "passive"))
      (node (ref "X1") (pin "12") (pinfunction "AL_12") (pintype "passive"))
    )
    (net (code "86") (name "unconnected-(IC1-PB6(XTAL1{slash}TOSC1)-Pad7)") (class "Default")
      (node (ref "IC1") (pin "7") (pinfunction "PB6(XTAL1/TOSC1)_7") (pintype "bidirectional"))
    )
    (net (code "87") (name "unconnected-(IC1-PB7(XTAL2{slash}TOSC2)-Pad8)") (class "Default")
      (node (ref "IC1") (pin "8") (pinfunction "PB7(XTAL2/TOSC2)_8") (pintype "bidirectional"))
    )
    (net (code "88") (name "unconnected-(IC3-O4-Pad15)") (class "Default")
      (node (ref "IC3") (pin "15") (pinfunction "O4_15") (pintype "open_collector"))
    )
    (net (code "89") (name "unconnected-(IC4-NC-Pad3)") (class "Default")
      (node (ref "IC4") (pin "3") (pinfunction "NC_3") (pintype "no_connect"))
    )
    (net (code "90") (name "unconnected-(IC4-NC1-Pad60)") (class "Default")
      (node (ref "IC4") (pin "60") (pinfunction "NC1_60") (pintype "no_connect"))
    )
    (net (code "91") (name "unconnected-(IC4-NC2-Pad61)") (class "Default")
      (node (ref "IC4") (pin "61") (pinfunction "NC2_61") (pintype "no_connect"))
    )
    (net (code "92") (name "unconnected-(IC4-NC3-Pad62)") (class "Default")
      (node (ref "IC4") (pin "62") (pinfunction "NC3_62") (pintype "no_connect"))
    )
    (net (code "93") (name "unconnected-(IC4-NC4-Pad78)") (class "Default")
      (node (ref "IC4") (pin "78") (pinfunction "NC4_78") (pintype "no_connect"))
    )
    (net (code "94") (name "unconnected-(IC4-NC5-Pad79)") (class "Default")
      (node (ref "IC4") (pin "79") (pinfunction "NC5_79") (pintype "no_connect"))
    )
    (net (code "95") (name "unconnected-(IC4-NC6-Pad80)") (class "Default")
      (node (ref "IC4") (pin "80") (pinfunction "NC6_80") (pintype "no_connect"))
    )
    (net (code "96") (name "unconnected-(IC4-RXLED-Pad72)") (class "Default")
      (node (ref "IC4") (pin "72") (pinfunction "RXLED_72") (pintype "output"))
    )
    (net (code "97") (name "unconnected-(IC4-TXLED-Pad73)") (class "Default")
      (node (ref "IC4") (pin "73") (pinfunction "TXLED_73") (pintype "output"))
    )
    (net (code "98") (name "unconnected-(IC4-XTLN-Pad75)") (class "Default")
      (node (ref "IC4") (pin "75") (pinfunction "XTLN_75") (pintype "output"))
    )
    (net (code "99") (name "unconnected-(IC4-XTLP-Pad76)") (class "Default")
      (node (ref "IC4") (pin "76") (pinfunction "XTLP_76") (pintype "output"))
    )
    (net (code "100") (name "unconnected-(U1-CLKOUT-Pad3)") (class "Default")
      (node (ref "U1") (pin "3") (pinfunction "CLKOUT_3") (pintype "bidirectional"))
    )
    (net (code "101") (name "unconnected-(U1-NC-Pad5)") (class "Default")
      (node (ref "U1") (pin "5") (pinfunction "NC_5") (pintype "bidirectional"))
    )
    (net (code "102") (name "unconnected-(U1-{slash}INT-Pad4)") (class "Default")
      (node (ref "U1") (pin "4") (pinfunction "/INT_4") (pintype "bidirectional"))
    )
    (net (code "103") (name "unconnected-(X1-CR-Pad6)") (class "Default")
      (node (ref "X1") (pin "6") (pinfunction "CR_6") (pintype "input"))
    )
    (net (code "104") (name "unconnected-(X1-NC{slash}4-Pad4)") (class "Default")
      (node (ref "X1") (pin "4") (pinfunction "NC/4_4") (pintype "input"))
    )
    (net (code "105") (name "unconnected-(X1-NC{slash}5-Pad5)") (class "Default")
      (node (ref "X1") (pin "5") (pinfunction "NC/5_5") (pintype "input"))
    )
  )
)
